# 02.net
KiCad netlist of a schematic drawn in EAGLE
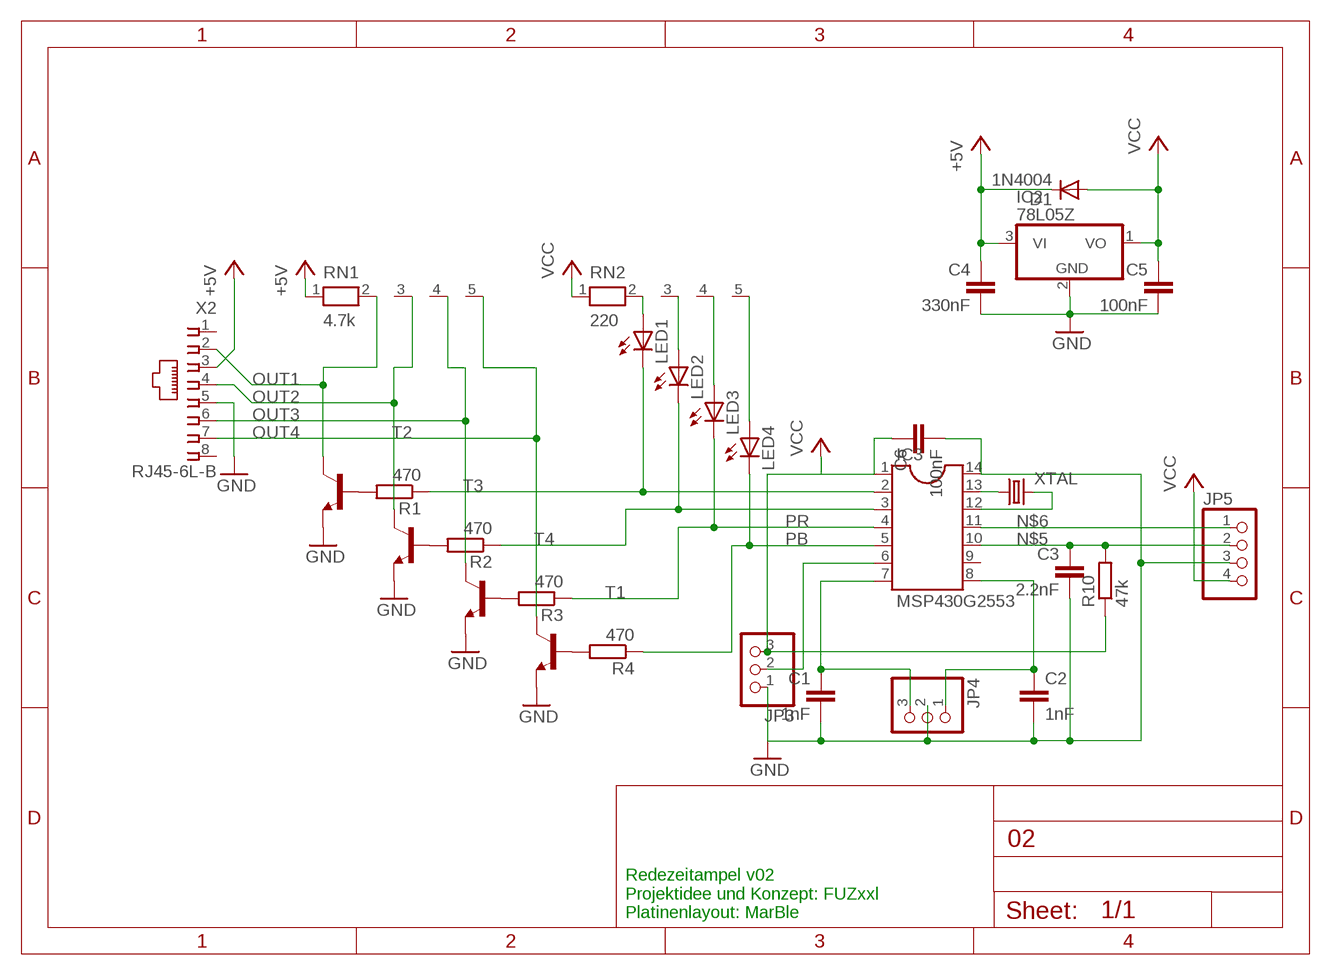
[diagram p0: schematic, sheet 1]

(export (version "E")
  (design (tool "Eeschema 10.0.6"))
  (components
    (comp (ref "C1")
      (value "1nF")
      (footprint "eagle-import:C025-024X044")
      (libsource (lib "eagle-import") (part "C-EU025-024X044"))
    )
    (comp (ref "C2")
      (value "1nF")
      (footprint "eagle-import:C025-024X044")
      (libsource (lib "eagle-import") (part "C-EU025-024X044"))
    )
    (comp (ref "C3")
      (value "2.2nF")
      (footprint "eagle-import:C025-024X044")
      (libsource (lib "eagle-import") (part "C-EU025-024X044"))
    )
    (comp (ref "C4")
      (value "330nF")
      (footprint "eagle-import:C050-024X044")
      (libsource (lib "eagle-import") (part "C-EU050-024X044"))
    )
    (comp (ref "C5")
      (value "100nF")
      (footprint "eagle-import:C050-024X044")
      (libsource (lib "eagle-import") (part "C-EU050-024X044"))
    )
    (comp (ref "C6")
      (value "100nF")
      (footprint "eagle-import:C050-024X044")
      (libsource (lib "eagle-import") (part "C-EU050-024X044"))
    )
    (comp (ref "D1")
      (value "1N4004")
      (footprint "eagle-import:DO41-10")
      (libsource (lib "eagle-import") (part "1N4004"))
    )
    (comp (ref "IC2")
      (value "78L05Z")
      (footprint "eagle-import:TO92")
      (libsource (lib "eagle-import") (part "78ZL05"))
    )
    (comp (ref "IC3")
      (value "MSP430G2553")
      (footprint "eagle-import:SOCKET-14")
      (libsource (lib "eagle-import") (part "DIL14S"))
    )
    (comp (ref "JP3")
      (value "PINHD-1X3")
      (footprint "eagle-import:1X03")
      (libsource (lib "eagle-import") (part "PINHD-1X3"))
    )
    (comp (ref "JP4")
      (value "PINHD-1X3")
      (footprint "eagle-import:1X03")
      (libsource (lib "eagle-import") (part "PINHD-1X3"))
    )
    (comp (ref "JP5")
      (value "PINHD-1X4")
      (footprint "eagle-import:1X04")
      (libsource (lib "eagle-import") (part "PINHD-1X4"))
    )
    (comp (ref "LED1")
      (value "LED5MM")
      (footprint "eagle-import:LED5MM")
      (libsource (lib "eagle-import") (part "LED5MM"))
    )
    (comp (ref "LED2")
      (value "LED5MM")
      (footprint "eagle-import:LED5MM")
      (libsource (lib "eagle-import") (part "LED5MM"))
    )
    (comp (ref "LED3")
      (value "LED5MM")
      (footprint "eagle-import:LED5MM")
      (libsource (lib "eagle-import") (part "LED5MM"))
    )
    (comp (ref "LED4")
      (value "LED5MM")
      (footprint "eagle-import:LED5MM")
      (libsource (lib "eagle-import") (part "LED5MM"))
    )
    (comp (ref "R1")
      (value "470")
      (footprint "eagle-import:0207_12")
      (libsource (lib "eagle-import") (part "R-EU_0207/12"))
    )
    (comp (ref "R2")
      (value "470")
      (footprint "eagle-import:0207_12")
      (libsource (lib "eagle-import") (part "R-EU_0207/12"))
    )
    (comp (ref "R3")
      (value "470")
      (footprint "eagle-import:0207_12")
      (libsource (lib "eagle-import") (part "R-EU_0207/12"))
    )
    (comp (ref "R4")
      (value "470")
      (footprint "eagle-import:0207_12")
      (libsource (lib "eagle-import") (part "R-EU_0207/12"))
    )
    (comp (ref "R10")
      (value "47k")
      (footprint "eagle-import:0207_7")
      (libsource (lib "eagle-import") (part "R-EU_0207/7"))
    )
    (comp (ref "RN1")
      (value "4.7k")
      (footprint "eagle-import:RN-5")
      (libsource (lib "eagle-import") (part "RN04"))
    )
    (comp (ref "RN2")
      (value "220")
      (footprint "eagle-import:RN-5")
      (libsource (lib "eagle-import") (part "RN04"))
    )
    (comp (ref "T1")
      (value "-NPN-TO92-EBC")
      (footprint "eagle-import:TO92-EBC")
      (libsource (lib "eagle-import") (part "-NPN-TO92-EBC"))
    )
    (comp (ref "T2")
      (value "-NPN-TO92-EBC")
      (footprint "eagle-import:TO92-EBC")
      (libsource (lib "eagle-import") (part "-NPN-TO92-EBC"))
    )
    (comp (ref "T3")
      (value "-NPN-TO92-EBC")
      (footprint "eagle-import:TO92-EBC")
      (libsource (lib "eagle-import") (part "-NPN-TO92-EBC"))
    )
    (comp (ref "T4")
      (value "-NPN-TO92-EBC")
      (footprint "eagle-import:TO92-EBC")
      (libsource (lib "eagle-import") (part "-NPN-TO92-EBC"))
    )
    (comp (ref "X2")
      (value "RJ45-6L-B")
      (footprint "eagle-import:RJ45-NO-SHIELD")
      (libsource (lib "eagle-import") (part "RJ45-6L-B"))
    )
    (comp (ref "XTAL")
      (value "CRYSTALTC26H")
      (footprint "eagle-import:TC26H")
      (libsource (lib "eagle-import") (part "CRYSTALTC26H"))
    )
  )
  (nets
    (net (code "1") (name "+5V") (class "Default")
      (node (ref "C4") (pin "1") (pinfunction "1_1") (pintype "passive"))
      (node (ref "D1") (pin "C") (pinfunction "C_C") (pintype "passive"))
      (node (ref "IC2") (pin "3") (pinfunction "VI_3") (pintype "input"))
      (node (ref "RN1") (pin "1") (pinfunction "1_1") (pintype "passive"))
      (node (ref "X2") (pin "3") (pinfunction "3_3") (pintype "passive"))
    )
    (net (code "2") (name "/N$5") (class "Default")
      (node (ref "C3") (pin "1") (pinfunction "1_1") (pintype "passive"))
      (node (ref "IC3") (pin "10") (pinfunction "10_10") (pintype "passive"))
      (node (ref "JP5") (pin "2") (pinfunction "2_2") (pintype "passive"))
      (node (ref "R10") (pin "2") (pinfunction "2_2") (pintype "passive"))
    )
    (net (code "3") (name "/N$6") (class "Default")
      (node (ref "IC3") (pin "11") (pinfunction "11_11") (pintype "passive"))
      (node (ref "JP5") (pin "1") (pinfunction "1_1") (pintype "passive"))
    )
    (net (code "4") (name "/OUT1") (class "Default")
      (node (ref "RN1") (pin "2") (pinfunction "2_2") (pintype "passive"))
      (node (ref "T2") (pin "C") (pinfunction "C_C") (pintype "passive"))
      (node (ref "X2") (pin "2") (pinfunction "2_2") (pintype "passive"))
    )
    (net (code "5") (name "/OUT2") (class "Default")
      (node (ref "RN1") (pin "3") (pinfunction "3_3") (pintype "passive"))
      (node (ref "T3") (pin "C") (pinfunction "C_C") (pintype "passive"))
      (node (ref "X2") (pin "4") (pinfunction "4_4") (pintype "passive"))
    )
    (net (code "6") (name "/OUT3") (class "Default")
      (node (ref "RN1") (pin "4") (pinfunction "4_4") (pintype "passive"))
      (node (ref "T4") (pin "C") (pinfunction "C_C") (pintype "passive"))
      (node (ref "X2") (pin "6") (pinfunction "6_6") (pintype "passive"))
    )
    (net (code "7") (name "/OUT4") (class "Default")
      (node (ref "RN1") (pin "5") (pinfunction "5_5") (pintype "passive"))
      (node (ref "T1") (pin "C") (pinfunction "C_C") (pintype "passive"))
      (node (ref "X2") (pin "7") (pinfunction "7_7") (pintype "passive"))
    )
    (net (code "8") (name "/PB") (class "Default")
      (node (ref "IC3") (pin "5") (pinfunction "5_5") (pintype "passive"))
      (node (ref "LED4") (pin "K") (pinfunction "C_K") (pintype "passive"))
      (node (ref "R4") (pin "1") (pinfunction "1_1") (pintype "passive"))
    )
    (net (code "9") (name "/PR") (class "Default")
      (node (ref "IC3") (pin "4") (pinfunction "4_4") (pintype "passive"))
      (node (ref "LED3") (pin "K") (pinfunction "C_K") (pintype "passive"))
      (node (ref "R3") (pin "1") (pinfunction "1_1") (pintype "passive"))
    )
    (net (code "10") (name "GND") (class "Default")
      (node (ref "C1") (pin "2") (pinfunction "2_2") (pintype "passive"))
      (node (ref "C2") (pin "2") (pinfunction "2_2") (pintype "passive"))
      (node (ref "C3") (pin "2") (pinfunction "2_2") (pintype "passive"))
      (node (ref "C4") (pin "2") (pinfunction "2_2") (pintype "passive"))
      (node (ref "C5") (pin "2") (pinfunction "2_2") (pintype "passive"))
      (node (ref "C6") (pin "2") (pinfunction "2_2") (pintype "passive"))
      (node (ref "IC2") (pin "2") (pinfunction "GND_2") (pintype "passive"))
      (node (ref "IC3") (pin "14") (pinfunction "14_14") (pintype "passive"))
      (node (ref "JP3") (pin "1") (pinfunction "1_1") (pintype "passive"))
      (node (ref "JP4") (pin "2") (pinfunction "2_2") (pintype "passive"))
      (node (ref "JP5") (pin "3") (pinfunction "3_3") (pintype "passive"))
      (node (ref "T1") (pin "E") (pinfunction "E_E") (pintype "passive"))
      (node (ref "T2") (pin "E") (pinfunction "E_E") (pintype "passive"))
      (node (ref "T3") (pin "E") (pinfunction "E_E") (pintype "passive"))
      (node (ref "T4") (pin "E") (pinfunction "E_E") (pintype "passive"))
      (node (ref "X2") (pin "5") (pinfunction "5_5") (pintype "passive"))
    )
    (net (code "11") (name "Net-(C1-Pad1)") (class "Default")
      (node (ref "C1") (pin "1") (pinfunction "1_1") (pintype "passive"))
      (node (ref "IC3") (pin "7") (pinfunction "7_7") (pintype "passive"))
      (node (ref "JP4") (pin "3") (pinfunction "3_3") (pintype "passive"))
    )
    (net (code "12") (name "Net-(C2-Pad1)") (class "Default")
      (node (ref "C2") (pin "1") (pinfunction "1_1") (pintype "passive"))
      (node (ref "IC3") (pin "8") (pinfunction "8_8") (pintype "passive"))
      (node (ref "JP4") (pin "1") (pinfunction "1_1") (pintype "passive"))
    )
    (net (code "13") (name "Net-(IC3-Pad6)") (class "Default")
      (node (ref "IC3") (pin "6") (pinfunction "6_6") (pintype "passive"))
      (node (ref "JP3") (pin "2") (pinfunction "2_2") (pintype "passive"))
    )
    (net (code "14") (name "Net-(IC3-Pad12)") (class "Default")
      (node (ref "IC3") (pin "12") (pinfunction "12_12") (pintype "passive"))
      (node (ref "XTAL") (pin "2") (pinfunction "2_2") (pintype "passive"))
    )
    (net (code "15") (name "Net-(IC3-Pad13)") (class "Default")
      (node (ref "IC3") (pin "13") (pinfunction "13_13") (pintype "passive"))
      (node (ref "XTAL") (pin "1") (pinfunction "1_1") (pintype "passive"))
    )
    (net (code "16") (name "Net-(LED1-C)") (class "Default")
      (node (ref "IC3") (pin "2") (pinfunction "2_2") (pintype "passive"))
      (node (ref "LED1") (pin "K") (pinfunction "C_K") (pintype "passive"))
      (node (ref "R1") (pin "1") (pinfunction "1_1") (pintype "passive"))
    )
    (net (code "17") (name "Net-(LED1-PadA)") (class "Default")
      (node (ref "LED1") (pin "A") (pinfunction "A_A") (pintype "passive"))
      (node (ref "RN2") (pin "2") (pinfunction "2_2") (pintype "passive"))
    )
    (net (code "18") (name "Net-(LED2-C)") (class "Default")
      (node (ref "IC3") (pin "3") (pinfunction "3_3") (pintype "passive"))
      (node (ref "LED2") (pin "K") (pinfunction "C_K") (pintype "passive"))
      (node (ref "R2") (pin "1") (pinfunction "1_1") (pintype "passive"))
    )
    (net (code "19") (name "Net-(LED2-PadA)") (class "Default")
      (node (ref "LED2") (pin "A") (pinfunction "A_A") (pintype "passive"))
      (node (ref "RN2") (pin "3") (pinfunction "3_3") (pintype "passive"))
    )
    (net (code "20") (name "Net-(LED3-PadA)") (class "Default")
      (node (ref "LED3") (pin "A") (pinfunction "A_A") (pintype "passive"))
      (node (ref "RN2") (pin "4") (pinfunction "4_4") (pintype "passive"))
    )
    (net (code "21") (name "Net-(LED4-PadA)") (class "Default")
      (node (ref "LED4") (pin "A") (pinfunction "A_A") (pintype "passive"))
      (node (ref "RN2") (pin "5") (pinfunction "5_5") (pintype "passive"))
    )
    (net (code "22") (name "Net-(R1-Pad2)") (class "Default")
      (node (ref "R1") (pin "2") (pinfunction "2_2") (pintype "passive"))
      (node (ref "T2") (pin "B") (pinfunction "B_B") (pintype "passive"))
    )
    (net (code "23") (name "Net-(R2-Pad2)") (class "Default")
      (node (ref "R2") (pin "2") (pinfunction "2_2") (pintype "passive"))
      (node (ref "T3") (pin "B") (pinfunction "B_B") (pintype "passive"))
    )
    (net (code "24") (name "Net-(R3-Pad2)") (class "Default")
      (node (ref "R3") (pin "2") (pinfunction "2_2") (pintype "passive"))
      (node (ref "T4") (pin "B") (pinfunction "B_B") (pintype "passive"))
    )
    (net (code "25") (name "Net-(R4-Pad2)") (class "Default")
      (node (ref "R4") (pin "2") (pinfunction "2_2") (pintype "passive"))
      (node (ref "T1") (pin "B") (pinfunction "B_B") (pintype "passive"))
    )
    (net (code "26") (name "VCC") (class "Default")
      (node (ref "C5") (pin "1") (pinfunction "1_1") (pintype "passive"))
      (node (ref "C6") (pin "1") (pinfunction "1_1") (pintype "passive"))
      (node (ref "D1") (pin "A") (pinfunction "A_A") (pintype "passive"))
      (node (ref "IC2") (pin "1") (pinfunction "VO_1") (pintype "passive"))
      (node (ref "IC3") (pin "1") (pinfunction "1_1") (pintype "passive"))
      (node (ref "JP3") (pin "3") (pinfunction "3_3") (pintype "passive"))
      (node (ref "JP5") (pin "4") (pinfunction "4_4") (pintype "passive"))
      (node (ref "R10") (pin "1") (pinfunction "1_1") (pintype "passive"))
      (node (ref "RN2") (pin "1") (pinfunction "1_1") (pintype "passive"))
    )
    (net (code "27") (name "unconnected-(IC3-Pad9)") (class "Default")
      (node (ref "IC3") (pin "9") (pinfunction "9_9") (pintype "passive"))
    )
    (net (code "28") (name "unconnected-(X2-Pad1)") (class "Default")
      (node (ref "X2") (pin "1") (pinfunction "1_1") (pintype "passive"))
    )
    (net (code "29") (name "unconnected-(X2-Pad8)") (class "Default")
      (node (ref "X2") (pin "8") (pinfunction "8_8") (pintype "passive"))
    )
  )
)
